# Mezzanine_CoVASPSy_v1re2.net
KiCad netlist of a schematic drawn in EAGLE
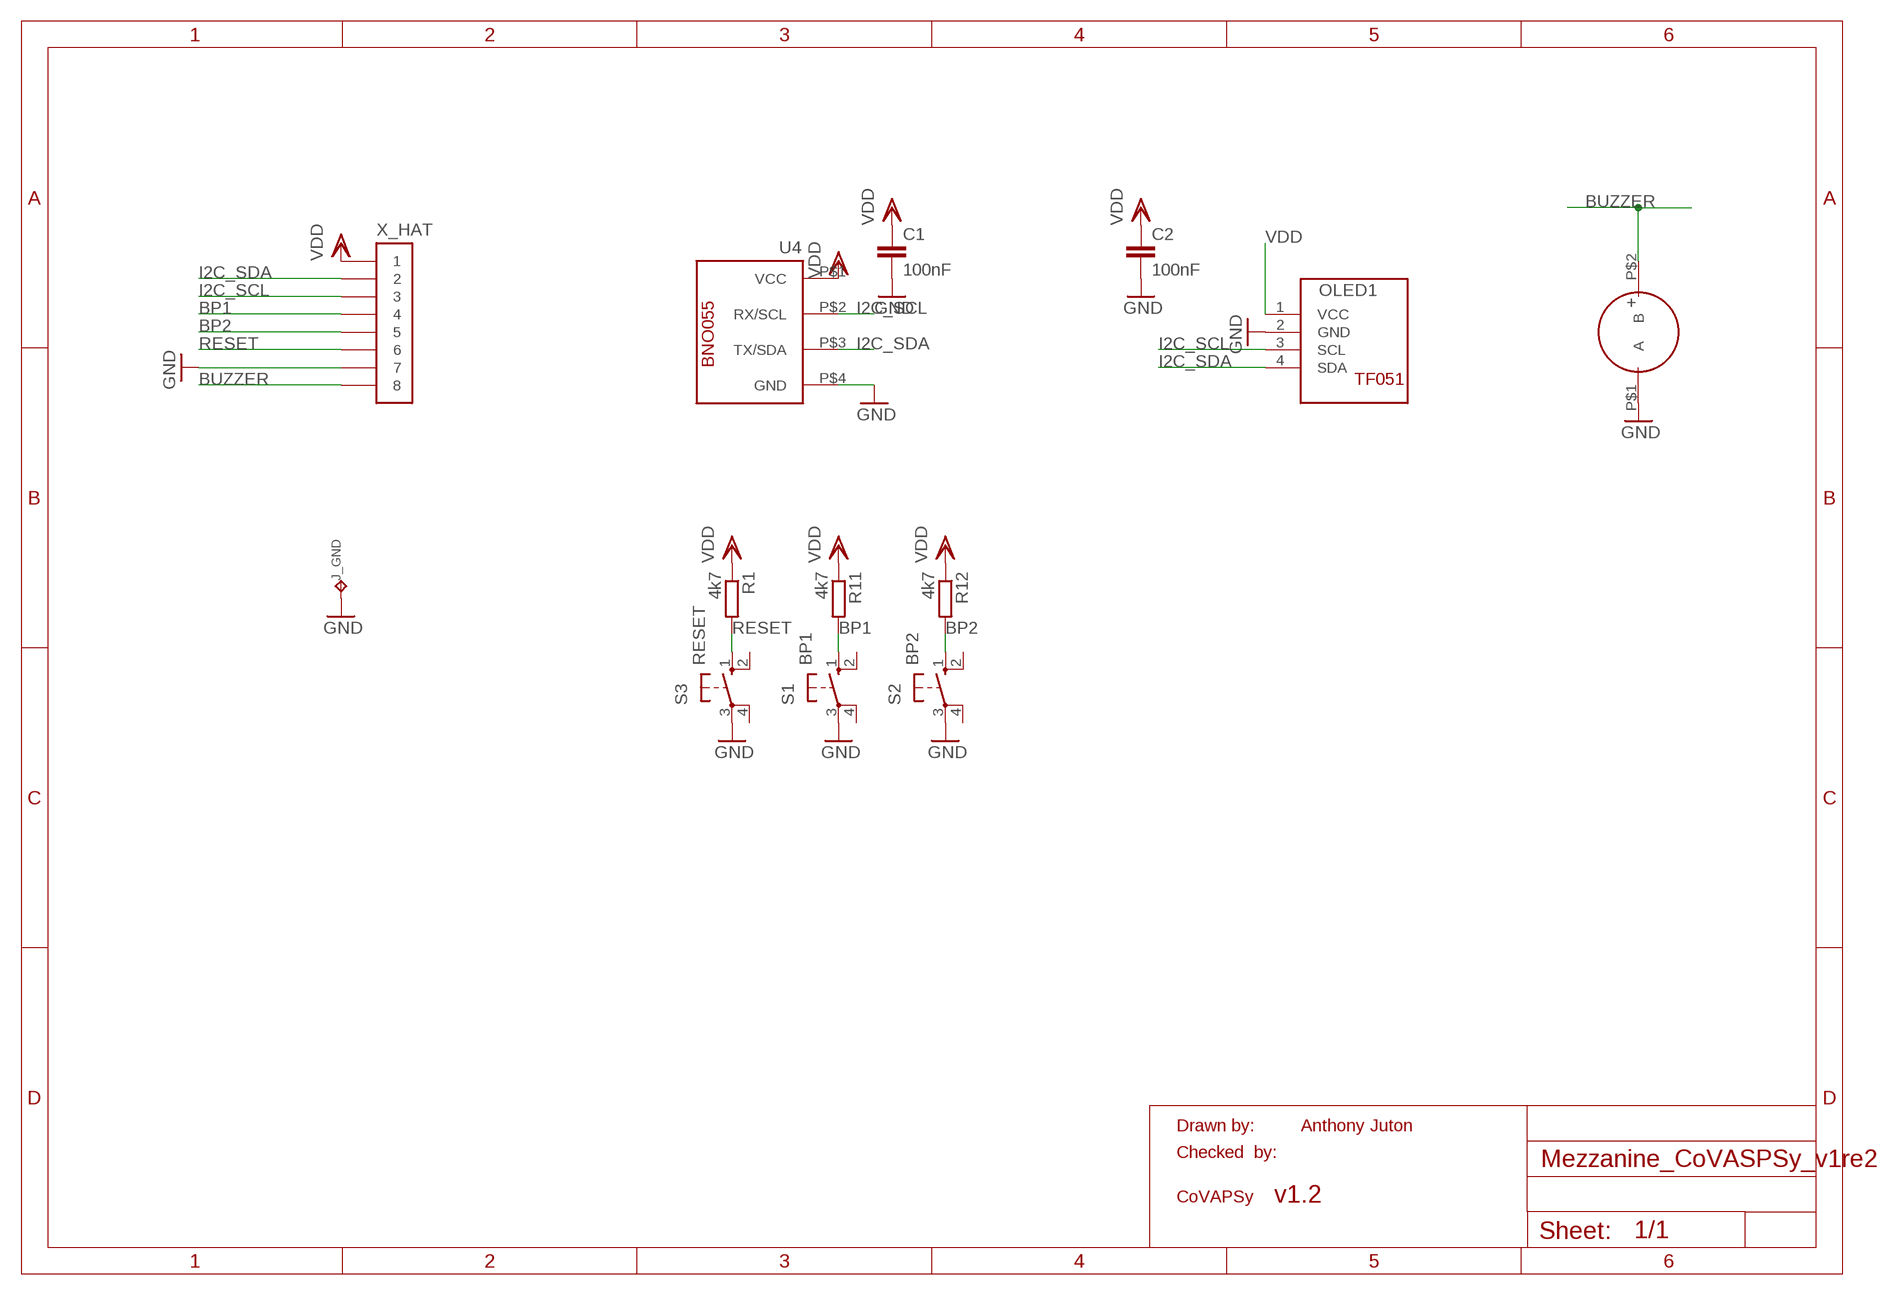
[diagram p0: schematic, sheet 1]

(export (version "E")
  (design (tool "Eeschema 10.0.6"))
  (components
    (comp (ref "BUZZER")
      (value "BUZZER_SMA13_P75")
      (footprint "eagle-import:BUZZER_SMA_13_P75")
      (libsource (lib "eagle-import") (part "BUZZER_SMA13_P75"))
    )
    (comp (ref "C1")
      (value "100nF")
      (footprint "eagle-import:C1206K")
      (libsource (lib "eagle-import") (part "C-EUC1206K"))
    )
    (comp (ref "C2")
      (value "100nF")
      (footprint "eagle-import:C1206K")
      (libsource (lib "eagle-import") (part "C-EUC1206K"))
    )
    (comp (ref "J_GND")
      (value "COSSE_POIGN")
      (footprint "eagle-import:COSSE_POIGNARD")
      (libsource (lib "eagle-import") (part "COSSE_POIGN"))
    )
    (comp (ref "OLED1")
      (value "ECRAN_OLED_TF051")
      (footprint "eagle-import:ECRAN_OLED_TF051")
      (libsource (lib "eagle-import") (part "ECRAN_OLED_TF051"))
    )
    (comp (ref "R1")
      (value "4k7")
      (footprint "eagle-import:M1206")
      (libsource (lib "eagle-import") (part "R-EU_M1206"))
    )
    (comp (ref "R11")
      (value "4k7")
      (footprint "eagle-import:M1206")
      (libsource (lib "eagle-import") (part "R-EU_M1206"))
    )
    (comp (ref "R12")
      (value "4k7")
      (footprint "eagle-import:M1206")
      (libsource (lib "eagle-import") (part "R-EU_M1206"))
    )
    (comp (ref "S1")
      (value "BP1")
      (footprint "eagle-import:B3F-10XX")
      (fields (field (name "MPN") "B3F-1000"))
      (libsource (lib "eagle-import") (part "10-XX"))
    )
    (comp (ref "S2")
      (value "BP2")
      (footprint "eagle-import:B3F-10XX")
      (fields (field (name "MPN") "B3F-1000"))
      (libsource (lib "eagle-import") (part "10-XX"))
    )
    (comp (ref "S3")
      (value "RESET")
      (footprint "eagle-import:B3F-10XX")
      (fields (field (name "MPN") "B3F-1000"))
      (libsource (lib "eagle-import") (part "10-XX"))
    )
    (comp (ref "U4")
      (value "MODULE_BNO055")
      (footprint "eagle-import:MODULE_BNO055")
      (libsource (lib "eagle-import") (part "MODULE_BNO055"))
    )
    (comp (ref "X_HAT")
      (value "MOLEX_8_COUDE")
      (footprint "eagle-import:MOLEX_8_COUDE")
      (libsource (lib "eagle-import") (part "MOLEX_8_COUDE"))
    )
  )
  (nets
    (net (code "1") (name "/BP1") (class "Default")
      (node (ref "R11") (pin "2") (pinfunction "2_2") (pintype "passive"))
      (node (ref "S1") (pin "1") (pinfunction "S_1") (pintype "passive"))
      (node (ref "X_HAT") (pin "P$4") (pinfunction "4_P$4") (pintype "bidirectional"))
    )
    (net (code "2") (name "/BP2") (class "Default")
      (node (ref "R12") (pin "2") (pinfunction "2_2") (pintype "passive"))
      (node (ref "S2") (pin "1") (pinfunction "S_1") (pintype "passive"))
      (node (ref "X_HAT") (pin "P$5") (pinfunction "5_P$5") (pintype "bidirectional"))
    )
    (net (code "3") (name "/BUZZER") (class "Default")
      (node (ref "BUZZER") (pin "P$2") (pinfunction "B_P$2") (pintype "bidirectional"))
      (node (ref "X_HAT") (pin "P$8") (pinfunction "8_P$8") (pintype "bidirectional"))
    )
    (net (code "4") (name "/I2C_SCL") (class "Default")
      (node (ref "OLED1") (pin "3") (pinfunction "SCL_3") (pintype "bidirectional"))
      (node (ref "U4") (pin "P$2") (pinfunction "RX/SCL_P$2") (pintype "bidirectional"))
      (node (ref "X_HAT") (pin "P$3") (pinfunction "3_P$3") (pintype "bidirectional"))
    )
    (net (code "5") (name "/I2C_SDA") (class "Default")
      (node (ref "OLED1") (pin "4") (pinfunction "SDA_4") (pintype "bidirectional"))
      (node (ref "U4") (pin "P$3") (pinfunction "TX/SDA_P$3") (pintype "bidirectional"))
      (node (ref "X_HAT") (pin "P$2") (pinfunction "2_P$2") (pintype "bidirectional"))
    )
    (net (code "6") (name "/RESET") (class "Default")
      (node (ref "R1") (pin "2") (pinfunction "2_2") (pintype "passive"))
      (node (ref "S3") (pin "1") (pinfunction "S_1") (pintype "passive"))
      (node (ref "X_HAT") (pin "P$6") (pinfunction "6_P$6") (pintype "bidirectional"))
    )
    (net (code "7") (name "GND") (class "Default")
      (node (ref "BUZZER") (pin "P$1") (pinfunction "A_P$1") (pintype "bidirectional"))
      (node (ref "C1") (pin "2") (pinfunction "2_2") (pintype "passive"))
      (node (ref "C2") (pin "2") (pinfunction "2_2") (pintype "passive"))
      (node (ref "J_GND") (pin "P$1") (pinfunction "P$1_P$1") (pintype "bidirectional"))
      (node (ref "OLED1") (pin "2") (pinfunction "GND_2") (pintype "bidirectional"))
      (node (ref "S1") (pin "3") (pinfunction "P_3") (pintype "passive"))
      (node (ref "S2") (pin "3") (pinfunction "P_3") (pintype "passive"))
      (node (ref "S3") (pin "3") (pinfunction "P_3") (pintype "passive"))
      (node (ref "U4") (pin "P$4") (pinfunction "GND_P$4") (pintype "bidirectional"))
      (node (ref "X_HAT") (pin "P$7") (pinfunction "7_P$7") (pintype "bidirectional"))
    )
    (net (code "8") (name "VDD") (class "Default")
      (node (ref "C1") (pin "1") (pinfunction "1_1") (pintype "passive"))
      (node (ref "C2") (pin "1") (pinfunction "1_1") (pintype "passive"))
      (node (ref "OLED1") (pin "1") (pinfunction "VCC_1") (pintype "bidirectional"))
      (node (ref "R1") (pin "1") (pinfunction "1_1") (pintype "passive"))
      (node (ref "R11") (pin "1") (pinfunction "1_1") (pintype "passive"))
      (node (ref "R12") (pin "1") (pinfunction "1_1") (pintype "passive"))
      (node (ref "U4") (pin "P$1") (pinfunction "VCC_P$1") (pintype "bidirectional"))
      (node (ref "X_HAT") (pin "P$1") (pinfunction "1_P$1") (pintype "bidirectional"))
    )
    (net (code "9") (name "unconnected-(S1-P1-Pad4)") (class "Default")
      (node (ref "S1") (pin "4") (pinfunction "P1_4") (pintype "passive"))
    )
    (net (code "10") (name "unconnected-(S1-S1-Pad2)") (class "Default")
      (node (ref "S1") (pin "2") (pinfunction "S1_2") (pintype "passive"))
    )
    (net (code "11") (name "unconnected-(S2-P1-Pad4)") (class "Default")
      (node (ref "S2") (pin "4") (pinfunction "P1_4") (pintype "passive"))
    )
    (net (code "12") (name "unconnected-(S2-S1-Pad2)") (class "Default")
      (node (ref "S2") (pin "2") (pinfunction "S1_2") (pintype "passive"))
    )
    (net (code "13") (name "unconnected-(S3-P1-Pad4)") (class "Default")
      (node (ref "S3") (pin "4") (pinfunction "P1_4") (pintype "passive"))
    )
    (net (code "14") (name "unconnected-(S3-S1-Pad2)") (class "Default")
      (node (ref "S3") (pin "2") (pinfunction "S1_2") (pintype "passive"))
    )
  )
)
